# JSDM_ESP32_DevKit_DS3231_HUB12_08_Single.net
KiCad netlist of a schematic drawn in EAGLE
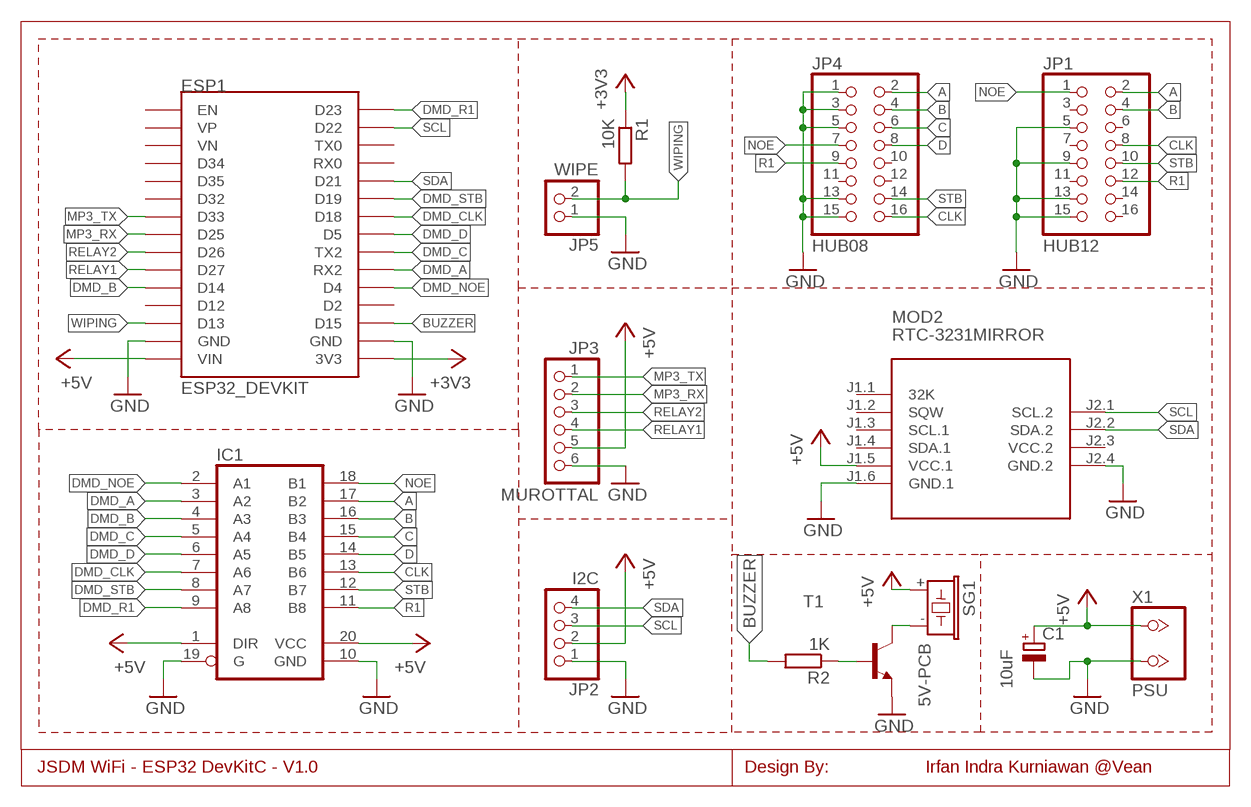
[diagram p0: schematic, sheet 1]

(export (version "E")
  (design (tool "Eeschema 10.0.6"))
  (components
    (comp (ref "C1")
      (value "10uF")
      (footprint "eagle-import:E3,5-8")
      (libsource (lib "eagle-import") (part "CPOL-EUE3.5-8"))
    )
    (comp (ref "ESP1")
      (value "ESP32_DEVKIT")
      (footprint "eagle-import:ESP32_DEVKIT")
      (libsource (lib "eagle-import") (part "ESP32_DEVKIT"))
    )
    (comp (ref "IC1")
      (value "74245SMD")
      (footprint "eagle-import:SO20")
      (libsource (lib "eagle-import") (part "74245SMD"))
    )
    (comp (ref "JP1")
      (value "HUB12")
      (footprint "eagle-import:2X08")
      (libsource (lib "eagle-import") (part "PINHD-2X8"))
    )
    (comp (ref "JP2")
      (value "I2C")
      (footprint "eagle-import:1X04")
      (libsource (lib "eagle-import") (part "PINHD-1X4"))
    )
    (comp (ref "JP3")
      (value "MUROTTAL")
      (footprint "eagle-import:1X06")
      (libsource (lib "eagle-import") (part "PINHD-1X6"))
    )
    (comp (ref "JP4")
      (value "HUB08")
      (footprint "eagle-import:2X08")
      (libsource (lib "eagle-import") (part "PINHD-2X8"))
    )
    (comp (ref "JP5")
      (value "WIPE")
      (footprint "eagle-import:1X02")
      (libsource (lib "eagle-import") (part "PINHD-1X2"))
    )
    (comp (ref "MOD2")
      (value "RTC-3231MIRROR")
      (footprint "eagle-import:RTC-DS3231-MIRROR")
      (libsource (lib "eagle-import") (part "RTC-3231MIRROR"))
    )
    (comp (ref "R1")
      (value "10K")
      (footprint "eagle-import:0207_7")
      (libsource (lib "eagle-import") (part "R-EU_0207/7"))
    )
    (comp (ref "R2")
      (value "1K")
      (footprint "eagle-import:0207_10")
      (libsource (lib "eagle-import") (part "R-EU_0207/10"))
    )
    (comp (ref "SG1")
      (value "5V-PCB")
      (footprint "eagle-import:5V")
      (libsource (lib "eagle-import") (part "5V-PCB"))
    )
    (comp (ref "T1")
      (value "BC317-NPN-TO92-EBC")
      (footprint "eagle-import:TO92-EBC")
      (libsource (lib "eagle-import") (part "-NPN-TO92-EBCBC317"))
    )
    (comp (ref "X1")
      (value "PSU")
      (footprint "eagle-import:TB2")
      (libsource (lib "eagle-import") (part "2PIN"))
    )
  )
  (nets
    (net (code "1") (name "+3V3") (class "Default")
      (node (ref "ESP1") (pin "3V3") (pinfunction "3V3_3V3") (pintype "bidirectional"))
      (node (ref "R1") (pin "1") (pinfunction "1_1") (pintype "passive"))
    )
    (net (code "2") (name "+5V") (class "Default")
      (node (ref "C1") (pin "+") (pinfunction "+_+") (pintype "passive"))
      (node (ref "ESP1") (pin "VIN") (pinfunction "VIN_VIN") (pintype "bidirectional"))
      (node (ref "IC1") (pin "1") (pinfunction "DIR_1") (pintype "input"))
      (node (ref "IC1") (pin "20") (pinfunction "VCC_20") (pintype "power_in"))
      (node (ref "JP2") (pin "2") (pinfunction "2_2") (pintype "passive"))
      (node (ref "JP3") (pin "5") (pinfunction "5_5") (pintype "passive"))
      (node (ref "MOD2") (pin "J1.5") (pinfunction "VCC.1_J1.5") (pintype "power_in"))
      (node (ref "SG1") (pin "+") (pinfunction "1_+") (pintype "passive"))
      (node (ref "X1") (pin "1") (pinfunction "1_1") (pintype "bidirectional"))
    )
    (net (code "3") (name "/VCC.2") (class "Default")
      (node (ref "MOD2") (pin "J2.3") (pinfunction "VCC.2_J2.3") (pintype "power_in"))
    )
    (net (code "4") (name "A") (class "Default")
      (node (ref "IC1") (pin "17") (pinfunction "B2_17") (pintype "bidirectional"))
      (node (ref "JP1") (pin "2") (pinfunction "2_2") (pintype "passive"))
      (node (ref "JP4") (pin "2") (pinfunction "2_2") (pintype "passive"))
    )
    (net (code "5") (name "B") (class "Default")
      (node (ref "IC1") (pin "16") (pinfunction "B3_16") (pintype "bidirectional"))
      (node (ref "JP1") (pin "4") (pinfunction "4_4") (pintype "passive"))
      (node (ref "JP4") (pin "4") (pinfunction "4_4") (pintype "passive"))
    )
    (net (code "6") (name "BUZZER") (class "Default")
      (node (ref "ESP1") (pin "D15") (pinfunction "D15_D15") (pintype "bidirectional"))
      (node (ref "R2") (pin "2") (pinfunction "2_2") (pintype "passive"))
    )
    (net (code "7") (name "C") (class "Default")
      (node (ref "IC1") (pin "15") (pinfunction "B4_15") (pintype "bidirectional"))
      (node (ref "JP4") (pin "6") (pinfunction "6_6") (pintype "passive"))
    )
    (net (code "8") (name "CLK") (class "Default")
      (node (ref "IC1") (pin "13") (pinfunction "B6_13") (pintype "bidirectional"))
      (node (ref "JP1") (pin "8") (pinfunction "8_8") (pintype "passive"))
      (node (ref "JP4") (pin "16") (pinfunction "16_16") (pintype "passive"))
    )
    (net (code "9") (name "D") (class "Default")
      (node (ref "IC1") (pin "14") (pinfunction "B5_14") (pintype "bidirectional"))
      (node (ref "JP4") (pin "8") (pinfunction "8_8") (pintype "passive"))
    )
    (net (code "10") (name "DMD_A") (class "Default")
      (node (ref "ESP1") (pin "RX2") (pinfunction "RX2_RX2") (pintype "bidirectional"))
      (node (ref "IC1") (pin "3") (pinfunction "A2_3") (pintype "bidirectional"))
    )
    (net (code "11") (name "DMD_B") (class "Default")
      (node (ref "ESP1") (pin "D14") (pinfunction "D14_D14") (pintype "bidirectional"))
      (node (ref "IC1") (pin "4") (pinfunction "A3_4") (pintype "bidirectional"))
    )
    (net (code "12") (name "DMD_C") (class "Default")
      (node (ref "ESP1") (pin "TX2") (pinfunction "TX2_TX2") (pintype "bidirectional"))
      (node (ref "IC1") (pin "5") (pinfunction "A4_5") (pintype "bidirectional"))
    )
    (net (code "13") (name "DMD_CLK") (class "Default")
      (node (ref "ESP1") (pin "D18") (pinfunction "D18_D18") (pintype "bidirectional"))
      (node (ref "IC1") (pin "7") (pinfunction "A6_7") (pintype "bidirectional"))
    )
    (net (code "14") (name "DMD_D") (class "Default")
      (node (ref "ESP1") (pin "D5") (pinfunction "D5_D5") (pintype "bidirectional"))
      (node (ref "IC1") (pin "6") (pinfunction "A5_6") (pintype "bidirectional"))
    )
    (net (code "15") (name "DMD_NOE") (class "Default")
      (node (ref "ESP1") (pin "D4") (pinfunction "D4_D4") (pintype "bidirectional"))
      (node (ref "IC1") (pin "2") (pinfunction "A1_2") (pintype "bidirectional"))
    )
    (net (code "16") (name "DMD_R1") (class "Default")
      (node (ref "ESP1") (pin "D23") (pinfunction "D23_D23") (pintype "bidirectional"))
      (node (ref "IC1") (pin "9") (pinfunction "A8_9") (pintype "bidirectional"))
    )
    (net (code "17") (name "DMD_STB") (class "Default")
      (node (ref "ESP1") (pin "D19") (pinfunction "D19_D19") (pintype "bidirectional"))
      (node (ref "IC1") (pin "8") (pinfunction "A7_8") (pintype "bidirectional"))
    )
    (net (code "18") (name "GND") (class "Default")
      (node (ref "C1") (pin "-") (pinfunction "-_-") (pintype "passive"))
      (node (ref "ESP1") (pin "GND@1") (pinfunction "GND_GND@1") (pintype "bidirectional"))
      (node (ref "ESP1") (pin "GND@2") (pinfunction "GND_GND@2") (pintype "bidirectional"))
      (node (ref "IC1") (pin "10") (pinfunction "GND_10") (pintype "power_in"))
      (node (ref "IC1") (pin "19") (pinfunction "G_19") (pintype "input"))
      (node (ref "JP1") (pin "13") (pinfunction "13_13") (pintype "passive"))
      (node (ref "JP1") (pin "15") (pinfunction "15_15") (pintype "passive"))
      (node (ref "JP1") (pin "5") (pinfunction "5_5") (pintype "passive"))
      (node (ref "JP1") (pin "9") (pinfunction "9_9") (pintype "passive"))
      (node (ref "JP2") (pin "1") (pinfunction "1_1") (pintype "passive"))
      (node (ref "JP3") (pin "6") (pinfunction "6_6") (pintype "passive"))
      (node (ref "JP4") (pin "1") (pinfunction "1_1") (pintype "passive"))
      (node (ref "JP4") (pin "13") (pinfunction "13_13") (pintype "passive"))
      (node (ref "JP4") (pin "15") (pinfunction "15_15") (pintype "passive"))
      (node (ref "JP4") (pin "3") (pinfunction "3_3") (pintype "passive"))
      (node (ref "JP4") (pin "5") (pinfunction "5_5") (pintype "passive"))
      (node (ref "JP5") (pin "1") (pinfunction "1_1") (pintype "passive"))
      (node (ref "MOD2") (pin "J1.6") (pinfunction "GND.1_J1.6") (pintype "power_in"))
      (node (ref "MOD2") (pin "J2.4") (pinfunction "GND.2_J2.4") (pintype "power_in"))
      (node (ref "T1") (pin "E") (pinfunction "E_E") (pintype "passive"))
      (node (ref "X1") (pin "2") (pinfunction "2_2") (pintype "bidirectional"))
    )
    (net (code "19") (name "MP3_RX") (class "Default")
      (node (ref "ESP1") (pin "D25") (pinfunction "D25_D25") (pintype "bidirectional"))
      (node (ref "JP3") (pin "2") (pinfunction "2_2") (pintype "passive"))
    )
    (net (code "20") (name "MP3_TX") (class "Default")
      (node (ref "ESP1") (pin "D33") (pinfunction "D33_D33") (pintype "bidirectional"))
      (node (ref "JP3") (pin "1") (pinfunction "1_1") (pintype "passive"))
    )
    (net (code "21") (name "NOE") (class "Default")
      (node (ref "IC1") (pin "18") (pinfunction "B1_18") (pintype "bidirectional"))
      (node (ref "JP1") (pin "1") (pinfunction "1_1") (pintype "passive"))
      (node (ref "JP4") (pin "7") (pinfunction "7_7") (pintype "passive"))
    )
    (net (code "22") (name "Net-(R2-Pad1)") (class "Default")
      (node (ref "R2") (pin "1") (pinfunction "1_1") (pintype "passive"))
      (node (ref "T1") (pin "B") (pinfunction "B_B") (pintype "passive"))
    )
    (net (code "23") (name "Net-(SG1-2)") (class "Default")
      (node (ref "SG1") (pin "-") (pinfunction "2_-") (pintype "passive"))
      (node (ref "T1") (pin "C") (pinfunction "C_C") (pintype "passive"))
    )
    (net (code "24") (name "R1") (class "Default")
      (node (ref "IC1") (pin "11") (pinfunction "B8_11") (pintype "bidirectional"))
      (node (ref "JP1") (pin "12") (pinfunction "12_12") (pintype "passive"))
      (node (ref "JP4") (pin "9") (pinfunction "9_9") (pintype "passive"))
    )
    (net (code "25") (name "RELAY1") (class "Default")
      (node (ref "ESP1") (pin "D27") (pinfunction "D27_D27") (pintype "bidirectional"))
      (node (ref "JP3") (pin "4") (pinfunction "4_4") (pintype "passive"))
    )
    (net (code "26") (name "RELAY2") (class "Default")
      (node (ref "ESP1") (pin "D26") (pinfunction "D26_D26") (pintype "bidirectional"))
      (node (ref "JP3") (pin "3") (pinfunction "3_3") (pintype "passive"))
    )
    (net (code "27") (name "SCL") (class "Default")
      (node (ref "ESP1") (pin "D22") (pinfunction "D22_D22") (pintype "bidirectional"))
      (node (ref "JP2") (pin "3") (pinfunction "3_3") (pintype "passive"))
      (node (ref "MOD2") (pin "J2.1") (pinfunction "SCL.2_J2.1") (pintype "bidirectional"))
    )
    (net (code "28") (name "SDA") (class "Default")
      (node (ref "ESP1") (pin "D21") (pinfunction "D21_D21") (pintype "bidirectional"))
      (node (ref "JP2") (pin "4") (pinfunction "4_4") (pintype "passive"))
      (node (ref "MOD2") (pin "J2.2") (pinfunction "SDA.2_J2.2") (pintype "bidirectional"))
    )
    (net (code "29") (name "STB") (class "Default")
      (node (ref "IC1") (pin "12") (pinfunction "B7_12") (pintype "bidirectional"))
      (node (ref "JP1") (pin "10") (pinfunction "10_10") (pintype "passive"))
      (node (ref "JP4") (pin "14") (pinfunction "14_14") (pintype "passive"))
    )
    (net (code "30") (name "WIPING") (class "Default")
      (node (ref "ESP1") (pin "D13") (pinfunction "D13_D13") (pintype "bidirectional"))
      (node (ref "JP5") (pin "2") (pinfunction "2_2") (pintype "passive"))
      (node (ref "R1") (pin "2") (pinfunction "2_2") (pintype "passive"))
    )
    (net (code "31") (name "unconnected-(ESP1-PadD2)") (class "Default")
      (node (ref "ESP1") (pin "D2") (pinfunction "D2_D2") (pintype "bidirectional"))
    )
    (net (code "32") (name "unconnected-(ESP1-PadD12)") (class "Default")
      (node (ref "ESP1") (pin "D12") (pinfunction "D12_D12") (pintype "bidirectional"))
    )
    (net (code "33") (name "unconnected-(ESP1-PadD32)") (class "Default")
      (node (ref "ESP1") (pin "D32") (pinfunction "D32_D32") (pintype "bidirectional"))
    )
    (net (code "34") (name "unconnected-(ESP1-PadD34)") (class "Default")
      (node (ref "ESP1") (pin "D34") (pinfunction "D34_D34") (pintype "bidirectional"))
    )
    (net (code "35") (name "unconnected-(ESP1-PadD35)") (class "Default")
      (node (ref "ESP1") (pin "D35") (pinfunction "D35_D35") (pintype "bidirectional"))
    )
    (net (code "36") (name "unconnected-(ESP1-PadEN)") (class "Default")
      (node (ref "ESP1") (pin "EN") (pinfunction "EN_EN") (pintype "bidirectional"))
    )
    (net (code "37") (name "unconnected-(ESP1-PadRX0)") (class "Default")
      (node (ref "ESP1") (pin "RX0") (pinfunction "RX0_RX0") (pintype "bidirectional"))
    )
    (net (code "38") (name "unconnected-(ESP1-PadTX0)") (class "Default")
      (node (ref "ESP1") (pin "TX0") (pinfunction "TX0_TX0") (pintype "bidirectional"))
    )
    (net (code "39") (name "unconnected-(ESP1-PadVN)") (class "Default")
      (node (ref "ESP1") (pin "VN") (pinfunction "VN_VN") (pintype "bidirectional"))
    )
    (net (code "40") (name "unconnected-(ESP1-PadVP)") (class "Default")
      (node (ref "ESP1") (pin "VP") (pinfunction "VP_VP") (pintype "bidirectional"))
    )
    (net (code "41") (name "unconnected-(JP1-Pad3)") (class "Default")
      (node (ref "JP1") (pin "3") (pinfunction "3_3") (pintype "passive"))
    )
    (net (code "42") (name "unconnected-(JP1-Pad6)") (class "Default")
      (node (ref "JP1") (pin "6") (pinfunction "6_6") (pintype "passive"))
    )
    (net (code "43") (name "unconnected-(JP1-Pad7)") (class "Default")
      (node (ref "JP1") (pin "7") (pinfunction "7_7") (pintype "passive"))
    )
    (net (code "44") (name "unconnected-(JP1-Pad11)") (class "Default")
      (node (ref "JP1") (pin "11") (pinfunction "11_11") (pintype "passive"))
    )
    (net (code "45") (name "unconnected-(JP1-Pad14)") (class "Default")
      (node (ref "JP1") (pin "14") (pinfunction "14_14") (pintype "passive"))
    )
    (net (code "46") (name "unconnected-(JP1-Pad16)") (class "Default")
      (node (ref "JP1") (pin "16") (pinfunction "16_16") (pintype "passive"))
    )
    (net (code "47") (name "unconnected-(JP4-Pad10)") (class "Default")
      (node (ref "JP4") (pin "10") (pinfunction "10_10") (pintype "passive"))
    )
    (net (code "48") (name "unconnected-(JP4-Pad11)") (class "Default")
      (node (ref "JP4") (pin "11") (pinfunction "11_11") (pintype "passive"))
    )
    (net (code "49") (name "unconnected-(JP4-Pad12)") (class "Default")
      (node (ref "JP4") (pin "12") (pinfunction "12_12") (pintype "passive"))
    )
    (net (code "50") (name "unconnected-(MOD2-32K-PadJ1.1)") (class "Default")
      (node (ref "MOD2") (pin "J1.1") (pinfunction "32K_J1.1") (pintype "bidirectional"))
    )
    (net (code "51") (name "unconnected-(MOD2-SCL.1-PadJ1.3)") (class "Default")
      (node (ref "MOD2") (pin "J1.3") (pinfunction "SCL.1_J1.3") (pintype "bidirectional"))
    )
    (net (code "52") (name "unconnected-(MOD2-SDA.1-PadJ1.4)") (class "Default")
      (node (ref "MOD2") (pin "J1.4") (pinfunction "SDA.1_J1.4") (pintype "bidirectional"))
    )
    (net (code "53") (name "unconnected-(MOD2-SQW-PadJ1.2)") (class "Default")
      (node (ref "MOD2") (pin "J1.2") (pinfunction "SQW_J1.2") (pintype "bidirectional"))
    )
  )
)
